# edge.net
KiCad netlist of a schematic drawn in Altium Designer
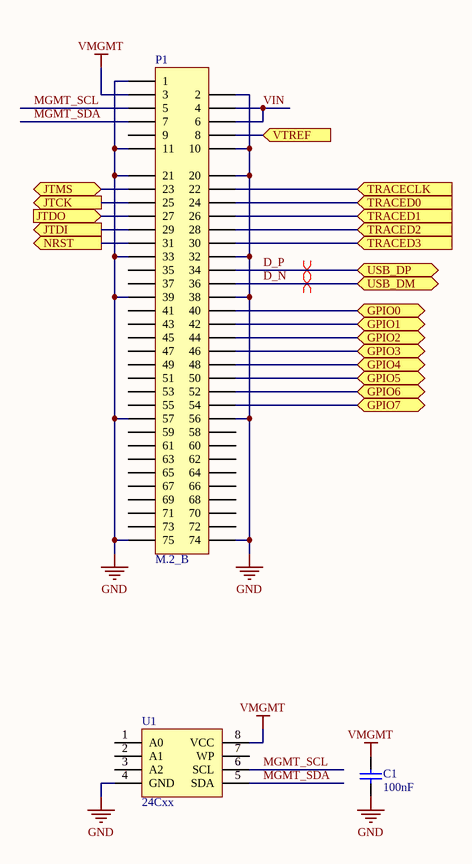
[diagram p0: edge.SchDoc]

(export (version "E")
  (design (tool "Eeschema 10.0.6"))
  (components
    (comp (ref "C1") (value "100nF") (footprint "0402") (libsource (lib "misc") (part "Capacitor")))
    (comp (ref "P1") (value "M.2_B") (footprint "M.2_B_EDGE") (libsource (lib "misc") (part "M.2_B")))
    (comp (ref "U1") (value "24Cxx") (footprint "SO8") (libsource (lib "misc") (part "24Cxx")))
  )
  (nets
    (net (code "1") (name "/D_N") (class "Default")
      (node (ref "P1") (pin "36") (pinfunction "36_36") (pintype "passive"))
    )
    (net (code "2") (name "/D_P") (class "Default")
      (node (ref "P1") (pin "34") (pinfunction "34_34") (pintype "passive"))
    )
    (net (code "3") (name "/GPIO0") (class "Default")
      (node (ref "P1") (pin "40") (pinfunction "40_40") (pintype "passive"))
    )
    (net (code "4") (name "/GPIO1") (class "Default")
      (node (ref "P1") (pin "42") (pinfunction "42_42") (pintype "passive"))
    )
    (net (code "5") (name "/GPIO2") (class "Default")
      (node (ref "P1") (pin "44") (pinfunction "44_44") (pintype "passive"))
    )
    (net (code "6") (name "/GPIO3") (class "Default")
      (node (ref "P1") (pin "46") (pinfunction "46_46") (pintype "passive"))
    )
    (net (code "7") (name "/GPIO4") (class "Default")
      (node (ref "P1") (pin "48") (pinfunction "48_48") (pintype "passive"))
    )
    (net (code "8") (name "/GPIO5") (class "Default")
      (node (ref "P1") (pin "50") (pinfunction "50_50") (pintype "passive"))
    )
    (net (code "9") (name "/GPIO6") (class "Default")
      (node (ref "P1") (pin "52") (pinfunction "52_52") (pintype "passive"))
    )
    (net (code "10") (name "/GPIO7") (class "Default")
      (node (ref "P1") (pin "54") (pinfunction "54_54") (pintype "passive"))
    )
    (net (code "11") (name "/JTCK") (class "Default")
      (node (ref "P1") (pin "25") (pinfunction "25_25") (pintype "passive"))
    )
    (net (code "12") (name "/JTDI") (class "Default")
      (node (ref "P1") (pin "29") (pinfunction "29_29") (pintype "passive"))
    )
    (net (code "13") (name "/JTDO") (class "Default")
      (node (ref "P1") (pin "27") (pinfunction "27_27") (pintype "passive"))
    )
    (net (code "14") (name "/JTMS") (class "Default")
      (node (ref "P1") (pin "23") (pinfunction "23_23") (pintype "passive"))
    )
    (net (code "15") (name "/MGMT_SCL") (class "Default")
      (node (ref "P1") (pin "5") (pinfunction "5_5") (pintype "passive"))
      (node (ref "U1") (pin "6") (pinfunction "SCL_6") (pintype "passive"))
    )
    (net (code "16") (name "/MGMT_SDA") (class "Default")
      (node (ref "P1") (pin "7") (pinfunction "7_7") (pintype "passive"))
      (node (ref "U1") (pin "5") (pinfunction "SDA_5") (pintype "passive"))
    )
    (net (code "17") (name "/NRST") (class "Default")
      (node (ref "P1") (pin "31") (pinfunction "31_31") (pintype "passive"))
    )
    (net (code "18") (name "/TRACECLK") (class "Default")
      (node (ref "P1") (pin "22") (pinfunction "22_22") (pintype "passive"))
    )
    (net (code "19") (name "/TRACED0") (class "Default")
      (node (ref "P1") (pin "24") (pinfunction "24_24") (pintype "passive"))
    )
    (net (code "20") (name "/TRACED1") (class "Default")
      (node (ref "P1") (pin "26") (pinfunction "26_26") (pintype "passive"))
    )
    (net (code "21") (name "/TRACED2") (class "Default")
      (node (ref "P1") (pin "28") (pinfunction "28_28") (pintype "passive"))
    )
    (net (code "22") (name "/TRACED3") (class "Default")
      (node (ref "P1") (pin "30") (pinfunction "30_30") (pintype "passive"))
    )
    (net (code "23") (name "/VIN") (class "Default")
      (node (ref "P1") (pin "4") (pinfunction "4_4") (pintype "passive"))
      (node (ref "P1") (pin "6") (pinfunction "6_6") (pintype "passive"))
    )
    (net (code "24") (name "/VTREF") (class "Default")
      (node (ref "P1") (pin "8") (pinfunction "8_8") (pintype "passive"))
    )
    (net (code "25") (name "GND") (class "Default")
      (node (ref "C1") (pin "1") (pinfunction "1_1") (pintype "passive"))
      (node (ref "P1") (pin "1") (pinfunction "1_1") (pintype "passive"))
      (node (ref "P1") (pin "10") (pinfunction "10_10") (pintype "passive"))
      (node (ref "P1") (pin "11") (pinfunction "11_11") (pintype "passive"))
      (node (ref "P1") (pin "2") (pinfunction "2_2") (pintype "passive"))
      (node (ref "P1") (pin "20") (pinfunction "20_20") (pintype "passive"))
      (node (ref "P1") (pin "21") (pinfunction "21_21") (pintype "passive"))
      (node (ref "P1") (pin "32") (pinfunction "32_32") (pintype "passive"))
      (node (ref "P1") (pin "33") (pinfunction "33_33") (pintype "passive"))
      (node (ref "P1") (pin "38") (pinfunction "38_38") (pintype "passive"))
      (node (ref "P1") (pin "39") (pinfunction "39_39") (pintype "passive"))
      (node (ref "P1") (pin "56") (pinfunction "56_56") (pintype "passive"))
      (node (ref "P1") (pin "57") (pinfunction "57_57") (pintype "passive"))
      (node (ref "P1") (pin "74") (pinfunction "74_74") (pintype "passive"))
      (node (ref "P1") (pin "75") (pinfunction "75_75") (pintype "passive"))
      (node (ref "U1") (pin "4") (pinfunction "GND_4") (pintype "passive"))
    )
    (net (code "26") (name "VMGMT") (class "Default")
      (node (ref "C1") (pin "2") (pinfunction "2_2") (pintype "passive"))
      (node (ref "P1") (pin "3") (pinfunction "3_3") (pintype "passive"))
      (node (ref "U1") (pin "8") (pinfunction "VCC_8") (pintype "passive"))
    )
    (net (code "27") (name "unconnected-(P1-Pad9)") (class "Default")
      (node (ref "P1") (pin "9") (pinfunction "9_9") (pintype "passive"))
    )
    (net (code "28") (name "unconnected-(P1-Pad35)") (class "Default")
      (node (ref "P1") (pin "35") (pinfunction "35_35") (pintype "passive"))
    )
    (net (code "29") (name "unconnected-(P1-Pad37)") (class "Default")
      (node (ref "P1") (pin "37") (pinfunction "37_37") (pintype "passive"))
    )
    (net (code "30") (name "unconnected-(P1-Pad41)") (class "Default")
      (node (ref "P1") (pin "41") (pinfunction "41_41") (pintype "passive"))
    )
    (net (code "31") (name "unconnected-(P1-Pad43)") (class "Default")
      (node (ref "P1") (pin "43") (pinfunction "43_43") (pintype "passive"))
    )
    (net (code "32") (name "unconnected-(P1-Pad45)") (class "Default")
      (node (ref "P1") (pin "45") (pinfunction "45_45") (pintype "passive"))
    )
    (net (code "33") (name "unconnected-(P1-Pad47)") (class "Default")
      (node (ref "P1") (pin "47") (pinfunction "47_47") (pintype "passive"))
    )
    (net (code "34") (name "unconnected-(P1-Pad49)") (class "Default")
      (node (ref "P1") (pin "49") (pinfunction "49_49") (pintype "passive"))
    )
    (net (code "35") (name "unconnected-(P1-Pad51)") (class "Default")
      (node (ref "P1") (pin "51") (pinfunction "51_51") (pintype "passive"))
    )
    (net (code "36") (name "unconnected-(P1-Pad53)") (class "Default")
      (node (ref "P1") (pin "53") (pinfunction "53_53") (pintype "passive"))
    )
    (net (code "37") (name "unconnected-(P1-Pad55)") (class "Default")
      (node (ref "P1") (pin "55") (pinfunction "55_55") (pintype "passive"))
    )
    (net (code "38") (name "unconnected-(P1-Pad58)") (class "Default")
      (node (ref "P1") (pin "58") (pinfunction "58_58") (pintype "passive"))
    )
    (net (code "39") (name "unconnected-(P1-Pad59)") (class "Default")
      (node (ref "P1") (pin "59") (pinfunction "59_59") (pintype "passive"))
    )
    (net (code "40") (name "unconnected-(P1-Pad60)") (class "Default")
      (node (ref "P1") (pin "60") (pinfunction "60_60") (pintype "passive"))
    )
    (net (code "41") (name "unconnected-(P1-Pad61)") (class "Default")
      (node (ref "P1") (pin "61") (pinfunction "61_61") (pintype "passive"))
    )
    (net (code "42") (name "unconnected-(P1-Pad62)") (class "Default")
      (node (ref "P1") (pin "62") (pinfunction "62_62") (pintype "passive"))
    )
    (net (code "43") (name "unconnected-(P1-Pad63)") (class "Default")
      (node (ref "P1") (pin "63") (pinfunction "63_63") (pintype "passive"))
    )
    (net (code "44") (name "unconnected-(P1-Pad64)") (class "Default")
      (node (ref "P1") (pin "64") (pinfunction "64_64") (pintype "passive"))
    )
    (net (code "45") (name "unconnected-(P1-Pad65)") (class "Default")
      (node (ref "P1") (pin "65") (pinfunction "65_65") (pintype "passive"))
    )
    (net (code "46") (name "unconnected-(P1-Pad66)") (class "Default")
      (node (ref "P1") (pin "66") (pinfunction "66_66") (pintype "passive"))
    )
    (net (code "47") (name "unconnected-(P1-Pad67)") (class "Default")
      (node (ref "P1") (pin "67") (pinfunction "67_67") (pintype "passive"))
    )
    (net (code "48") (name "unconnected-(P1-Pad68)") (class "Default")
      (node (ref "P1") (pin "68") (pinfunction "68_68") (pintype "passive"))
    )
    (net (code "49") (name "unconnected-(P1-Pad69)") (class "Default")
      (node (ref "P1") (pin "69") (pinfunction "69_69") (pintype "passive"))
    )
    (net (code "50") (name "unconnected-(P1-Pad70)") (class "Default")
      (node (ref "P1") (pin "70") (pinfunction "70_70") (pintype "passive"))
    )
    (net (code "51") (name "unconnected-(P1-Pad71)") (class "Default")
      (node (ref "P1") (pin "71") (pinfunction "71_71") (pintype "passive"))
    )
    (net (code "52") (name "unconnected-(P1-Pad72)") (class "Default")
      (node (ref "P1") (pin "72") (pinfunction "72_72") (pintype "passive"))
    )
    (net (code "53") (name "unconnected-(P1-Pad73)") (class "Default")
      (node (ref "P1") (pin "73") (pinfunction "73_73") (pintype "passive"))
    )
    (net (code "54") (name "unconnected-(U1-A0-Pad1)") (class "Default")
      (node (ref "U1") (pin "1") (pinfunction "A0_1") (pintype "passive"))
    )
    (net (code "55") (name "unconnected-(U1-A1-Pad2)") (class "Default")
      (node (ref "U1") (pin "2") (pinfunction "A1_2") (pintype "passive"))
    )
    (net (code "56") (name "unconnected-(U1-A2-Pad3)") (class "Default")
      (node (ref "U1") (pin "3") (pinfunction "A2_3") (pintype "passive"))
    )
    (net (code "57") (name "unconnected-(U1-WP-Pad7)") (class "Default")
      (node (ref "U1") (pin "7") (pinfunction "WP_7") (pintype "passive"))
    )
  )
)
